# top.net
KiCad netlist of a schematic drawn in Altium Designer
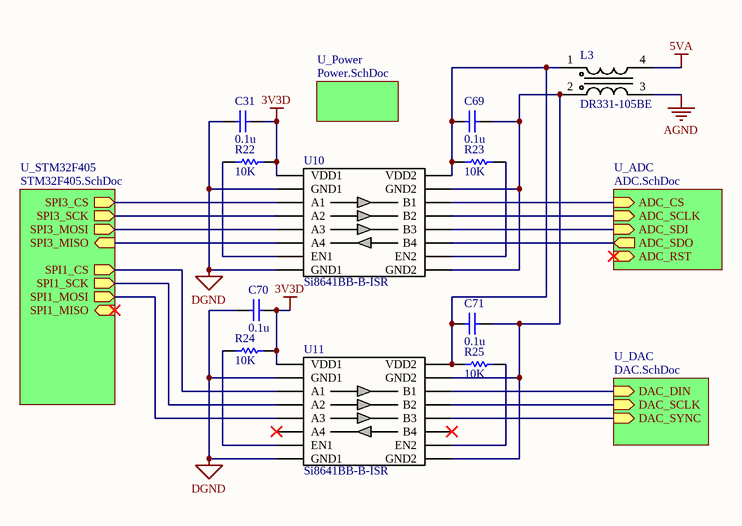
[diagram p0: top.SchDoc]

(export (version "E")
  (design (tool "Eeschema 10.0.6"))
  (components
    (comp (ref "C31")
      (value "0.1u")
      (footprint "CAPC1608X90N")
      (description "Capacitor")
      (fields (field (name "Comment") "Cap") (field (name "PUBLISHER") "Altium Limited"))
      (libsource (lib "IOBoard_Low") (part "Cap"))
    )
    (comp (ref "C69")
      (value "0.1u")
      (footprint "CAPC1608X90N")
      (description "Capacitor")
      (fields (field (name "Comment") "Cap") (field (name "PUBLISHER") "Altium Limited"))
      (libsource (lib "IOBoard_Low") (part "Cap"))
    )
    (comp (ref "C70")
      (value "0.1u")
      (footprint "CAPC1608X90N")
      (description "Capacitor")
      (fields (field (name "Comment") "Cap") (field (name "PUBLISHER") "Altium Limited"))
      (libsource (lib "IOBoard_Low") (part "Cap"))
    )
    (comp (ref "C71")
      (value "0.1u")
      (footprint "CAPC1608X90N")
      (description "Capacitor")
      (fields (field (name "Comment") "Cap") (field (name "PUBLISHER") "Altium Limited"))
      (libsource (lib "IOBoard_Low") (part "Cap"))
    )
    (comp (ref "L3")
      (value "DR331-105BE")
      (footprint "DR331-105BE")
      (description "Common mode choke 1mH 0.5A")
      (libsource (lib "IOBoard_Low") (part "DR331-105BE"))
    )
    (comp (ref "R22")
      (value "10K")
      (footprint "RESC1608X55N")
      (description "Resistor")
      (fields (field (name "Comment") "Res1") (field (name "PUBLISHER") "Altium Limited"))
      (libsource (lib "IOBoard") (part "Res1"))
    )
    (comp (ref "R23")
      (value "10K")
      (footprint "RESC1608X55N")
      (description "Resistor")
      (fields (field (name "Comment") "Res1") (field (name "PUBLISHER") "Altium Limited"))
      (libsource (lib "IOBoard") (part "Res1"))
    )
    (comp (ref "R24")
      (value "10K")
      (footprint "RESC1608X55N")
      (description "Resistor")
      (fields (field (name "Comment") "Res1") (field (name "PUBLISHER") "Altium Limited"))
      (libsource (lib "IOBoard") (part "Res1"))
    )
    (comp (ref "R25")
      (value "10K")
      (footprint "RESC1608X55N")
      (description "Resistor")
      (fields (field (name "Comment") "Res1") (field (name "PUBLISHER") "Altium Limited"))
      (libsource (lib "IOBoard") (part "Res1"))
    )
    (comp (ref "U10")
      (value "Si8641BB-B-ISR")
      (footprint "SOIC127P600X175-16AN")
      (description "isolator for SPI 3 forward 1 reverse isolator")
      (libsource (lib "IOBoard") (part "Si8641BB-B-ISR"))
    )
    (comp (ref "U11")
      (value "Si8641BB-B-ISR")
      (footprint "SOIC127P600X175-16AN")
      (description "isolator for SPI 3 forward 1 reverse isolator")
      (libsource (lib "IOBoard") (part "Si8641BB-B-ISR"))
    )
  )
  (nets
    (net (code "1") (name "/ADC_CS") (class "Default")
      (node (ref "U10") (pin "14") (pinfunction "B1_14") (pintype "passive"))
    )
    (net (code "3") (name "/ADC_SCLK") (class "Default")
      (node (ref "U10") (pin "13") (pinfunction "B2_13") (pintype "passive"))
    )
    (net (code "4") (name "/ADC_SDI") (class "Default")
      (node (ref "U10") (pin "12") (pinfunction "B3_12") (pintype "passive"))
    )
    (net (code "5") (name "/ADC_SDO") (class "Default")
      (node (ref "U10") (pin "11") (pinfunction "B4_11") (pintype "passive"))
    )
    (net (code "6") (name "/DAC_DIN") (class "Default")
      (node (ref "U11") (pin "14") (pinfunction "B1_14") (pintype "passive"))
    )
    (net (code "7") (name "/DAC_SCLK") (class "Default")
      (node (ref "U11") (pin "13") (pinfunction "B2_13") (pintype "passive"))
    )
    (net (code "8") (name "/DAC_SYNC") (class "Default")
      (node (ref "U11") (pin "12") (pinfunction "B3_12") (pintype "passive"))
    )
    (net (code "9") (name "/SPI1_CS") (class "Default")
      (node (ref "U11") (pin "3") (pinfunction "A1_3") (pintype "passive"))
    )
    (net (code "11") (name "/SPI1_MOSI") (class "Default")
      (node (ref "U11") (pin "5") (pinfunction "A3_5") (pintype "passive"))
    )
    (net (code "12") (name "/SPI1_SCK") (class "Default")
      (node (ref "U11") (pin "4") (pinfunction "A2_4") (pintype "passive"))
    )
    (net (code "13") (name "/SPI3_CS") (class "Default")
      (node (ref "U10") (pin "3") (pinfunction "A1_3") (pintype "passive"))
    )
    (net (code "14") (name "/SPI3_MISO") (class "Default")
      (node (ref "U10") (pin "6") (pinfunction "A4_6") (pintype "passive"))
    )
    (net (code "15") (name "/SPI3_MOSI") (class "Default")
      (node (ref "U10") (pin "5") (pinfunction "A3_5") (pintype "passive"))
    )
    (net (code "16") (name "/SPI3_SCK") (class "Default")
      (node (ref "U10") (pin "4") (pinfunction "A2_4") (pintype "passive"))
    )
    (net (code "17") (name "3V3D") (class "Default")
      (node (ref "C31") (pin "1") (pinfunction "1_1") (pintype "passive"))
      (node (ref "C70") (pin "1") (pinfunction "1_1") (pintype "passive"))
      (node (ref "R22") (pin "2") (pinfunction "2_2") (pintype "passive"))
      (node (ref "R24") (pin "2") (pinfunction "2_2") (pintype "passive"))
      (node (ref "U10") (pin "1") (pinfunction "VDD1_1") (pintype "passive"))
      (node (ref "U11") (pin "1") (pinfunction "VDD1_1") (pintype "passive"))
    )
    (net (code "18") (name "5VA") (class "Default")
      (node (ref "L3") (pin "4") (pinfunction "VOUT+_4") (pintype "power_in"))
    )
    (net (code "19") (name "AGND") (class "Default")
      (node (ref "L3") (pin "3") (pinfunction "VOUT+_3") (pintype "power_in"))
    )
    (net (code "20") (name "DGND") (class "Default")
      (node (ref "C31") (pin "2") (pinfunction "2_2") (pintype "passive"))
      (node (ref "C70") (pin "2") (pinfunction "2_2") (pintype "passive"))
      (node (ref "U10") (pin "2") (pinfunction "GND1_2") (pintype "passive"))
      (node (ref "U10") (pin "8") (pinfunction "GND1_8") (pintype "passive"))
      (node (ref "U11") (pin "2") (pinfunction "GND1_2") (pintype "passive"))
      (node (ref "U11") (pin "8") (pinfunction "GND1_8") (pintype "passive"))
    )
    (net (code "21") (name "Net-(C69-Pad2)") (class "Default")
      (node (ref "C69") (pin "2") (pinfunction "2_2") (pintype "passive"))
      (node (ref "C71") (pin "1") (pinfunction "1_1") (pintype "passive"))
      (node (ref "L3") (pin "2") (pinfunction "VOUT+_2") (pintype "power_in"))
      (node (ref "U10") (pin "15") (pinfunction "GND2_15") (pintype "passive"))
      (node (ref "U10") (pin "9") (pinfunction "GND2_9") (pintype "passive"))
      (node (ref "U11") (pin "15") (pinfunction "GND2_15") (pintype "passive"))
      (node (ref "U11") (pin "9") (pinfunction "GND2_9") (pintype "passive"))
    )
    (net (code "22") (name "Net-(U10-EN1)") (class "Default")
      (node (ref "R22") (pin "1") (pinfunction "1_1") (pintype "passive"))
      (node (ref "U10") (pin "7") (pinfunction "EN1_7") (pintype "passive"))
    )
    (net (code "23") (name "Net-(U10-EN2)") (class "Default")
      (node (ref "R23") (pin "2") (pinfunction "2_2") (pintype "passive"))
      (node (ref "U10") (pin "10") (pinfunction "EN2_10") (pintype "passive"))
    )
    (net (code "24") (name "Net-(U10-VDD2)") (class "Default")
      (node (ref "C69") (pin "1") (pinfunction "1_1") (pintype "passive"))
      (node (ref "C71") (pin "2") (pinfunction "2_2") (pintype "passive"))
      (node (ref "L3") (pin "1") (pinfunction "VOUT+_1") (pintype "power_in"))
      (node (ref "R23") (pin "1") (pinfunction "1_1") (pintype "passive"))
      (node (ref "R25") (pin "1") (pinfunction "1_1") (pintype "passive"))
      (node (ref "U10") (pin "16") (pinfunction "VDD2_16") (pintype "passive"))
      (node (ref "U11") (pin "16") (pinfunction "VDD2_16") (pintype "passive"))
    )
    (net (code "25") (name "Net-(U11-EN1)") (class "Default")
      (node (ref "R24") (pin "1") (pinfunction "1_1") (pintype "passive"))
      (node (ref "U11") (pin "7") (pinfunction "EN1_7") (pintype "passive"))
    )
    (net (code "26") (name "Net-(U11-EN2)") (class "Default")
      (node (ref "R25") (pin "2") (pinfunction "2_2") (pintype "passive"))
      (node (ref "U11") (pin "10") (pinfunction "EN2_10") (pintype "passive"))
    )
    (net (code "27") (name "unconnected-(U11-A4-Pad6)") (class "Default")
      (node (ref "U11") (pin "6") (pinfunction "A4_6") (pintype "passive+no_connect"))
    )
    (net (code "28") (name "unconnected-(U11-B4-Pad11)") (class "Default")
      (node (ref "U11") (pin "11") (pinfunction "B4_11") (pintype "passive+no_connect"))
    )
  )
)
